# RX_V1.net
KiCad netlist of a schematic drawn in Altium Designer
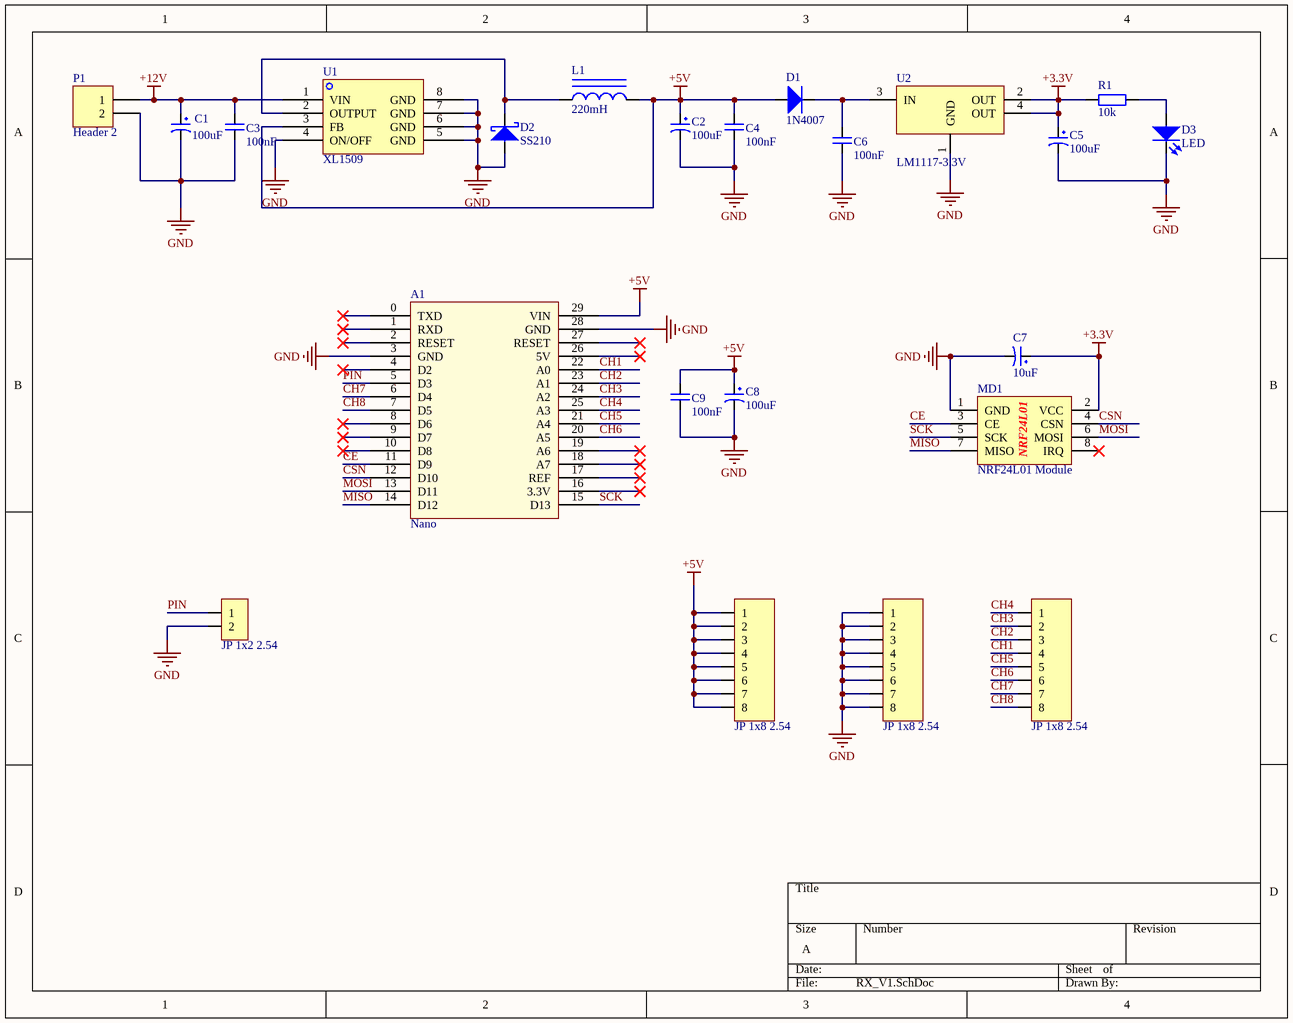
[diagram p0: RX_V1.SchDoc]

(export (version "E")
  (design (tool "Eeschema 10.0.6"))
  (components
    (comp (ref "A1")
      (value "Nano")
      (footprint "Arduino nano")
      (libsource (lib "Altium_Lib_by_KhueNguyenCreator") (part "Arduino Nano"))
    )
    (comp (ref "C1")
      (value "100uF")
      (footprint "tu hoa 5mm")
      (description "Cắm")
      (libsource (lib "Altium_Lib_by_KhueNguyenCreator") (part "Tu Hoa 100uF 25V 6x11"))
    )
    (comp (ref "C2")
      (value "100uF")
      (footprint "tu hoa 5mm")
      (description "Cắm")
      (libsource (lib "Altium_Lib_by_KhueNguyenCreator") (part "Tu Hoa 100uF 25V 6x11"))
    )
    (comp (ref "C3")
      (value "100nF")
      (footprint "CN1")
      (libsource (lib "Electronic4u") (part "Cap_Non-Polar"))
    )
    (comp (ref "C4")
      (value "100nF")
      (footprint "CN1")
      (libsource (lib "Electronic4u") (part "Cap_Non-Polar"))
    )
    (comp (ref "C5")
      (value "100uF")
      (footprint "tu hoa 5mm")
      (description "Cắm")
      (libsource (lib "Altium_Lib_by_KhueNguyenCreator") (part "Tu Hoa 100uF 25V 6x11"))
    )
    (comp (ref "C6")
      (value "100nF")
      (footprint "CN1")
      (libsource (lib "Electronic4u") (part "Cap_Non-Polar"))
    )
    (comp (ref "C7")
      (value "10uF")
      (footprint "tu hoa 5mm")
      (description "Cắm")
      (libsource (lib "") (part "Tu Hoa 100uF 25V 6x11_1"))
    )
    (comp (ref "C8")
      (value "100uF")
      (footprint "tu hoa 5mm")
      (description "Cắm")
      (libsource (lib "Altium_Lib_by_KhueNguyenCreator") (part "Tu Hoa 100uF 25V 6x11"))
    )
    (comp (ref "C9")
      (value "100nF")
      (footprint "CN1")
      (libsource (lib "Electronic4u") (part "Cap_Non-Polar"))
    )
    (comp (ref "D1")
      (value "1N4007")
      (footprint "DO-201AD-V")
      (description "Diode Standard")
      (fields (field (name "PART NUMBER") "LED 3 ly Single Colour"))
      (libsource (lib "Electronic4u") (part "Diode Standard"))
    )
    (comp (ref "D2")
      (value "SS210")
      (footprint "DO-214AC")
      (description "Diode Schottky")
      (fields (field (name "PART NUMBER") "LED 3 ly Single Colour"))
      (libsource (lib "Electronic4u") (part "Diode Schottky"))
    )
    (comp (ref "D3")
      (value "LED")
      (footprint "LED-3MM RED")
      (description "LED Single")
      (libsource (lib "Electronic4u") (part "LED"))
    )
    (comp (ref "JP1")
      (value "JP 1x2 2.54")
      (footprint "JP 1x2 DT")
      (description "Cắm")
      (libsource (lib "Altium_Lib_by_KhueNguyenCreator") (part "JP 1x2 2.54 Duc Thang"))
    )
    (comp (ref "JP2")
      (value "JP 1x8 2.54")
      (footprint "JP 1x8 DT")
      (description "Cắm")
      (libsource (lib "Altium_Lib_by_KhueNguyenCreator") (part "JP 1x8 2.54 Duc Thang"))
    )
    (comp (ref "JP3")
      (value "JP 1x8 2.54")
      (footprint "JP 1x8 DT")
      (description "Cắm")
      (libsource (lib "Altium_Lib_by_KhueNguyenCreator") (part "JP 1x8 2.54 Duc Thang"))
    )
    (comp (ref "JP4")
      (value "JP 1x8 2.54")
      (footprint "JP 1x8 DT")
      (description "Cắm")
      (libsource (lib "Altium_Lib_by_KhueNguyenCreator") (part "JP 1x8 2.54 Duc Thang"))
    )
    (comp (ref "L1")
      (value "220mH")
      (footprint "INDUCTOR SMD 7342 7.3X7.3X4.2mm")
      (description "Magnetic-Core Inductor")
      (libsource (lib "Electronic4u") (part "Inductor Iron"))
    )
    (comp (ref "MD1")
      (value "NRF24L01 Module")
      (footprint "NRF24L01")
      (libsource (lib "Altium_Lib_by_KhueNguyenCreator") (part "NRF24L01 Module"))
    )
    (comp (ref "P1")
      (value "Header 2")
      (footprint "HED2T")
      (description "Header, 2-Pin")
      (fields (field (name "PUBLISHER") "Altium Limited"))
      (libsource (lib "Electronic4u") (part "Header 2"))
    )
    (comp (ref "R1")
      (value "10k")
      (footprint "RESISTOR 1/4W")
      (libsource (lib "Electronic4u") (part "Resistor"))
    )
    (comp (ref "U1")
      (value "XL1509")
      (footprint "SOP8")
      (description "IC power sop8")
      (libsource (lib "FMS_PcbLib1") (part "XL1509"))
    )
    (comp (ref "U2")
      (value "LM1117-3.3V")
      (footprint "SOT223-4N")
      (description "800mA Low-Dropout Linear Regulator")
      (fields (field (name "CREATOR") "Nguyen Ba Bien"))
      (libsource (lib "Electronic4u") (part "LM1117"))
    )
  )
  (nets
    (net (code "1") (name "+3.3V") (class "Default")
      (node (ref "C5") (pin "1") (pinfunction "1_1") (pintype "passive"))
      (node (ref "C7") (pin "1") (pinfunction "1_1") (pintype "passive"))
      (node (ref "MD1") (pin "2") (pinfunction "VCC_2") (pintype "passive"))
      (node (ref "R1") (pin "1") (pinfunction "1_1") (pintype "passive"))
      (node (ref "U2") (pin "2") (pinfunction "OUT_2") (pintype "passive"))
      (node (ref "U2") (pin "4") (pinfunction "OUT_4") (pintype "passive"))
    )
    (net (code "2") (name "+5V") (class "Default")
      (node (ref "A1") (pin "29") (pinfunction "VIN_29") (pintype "passive"))
      (node (ref "C2") (pin "1") (pinfunction "1_1") (pintype "passive"))
      (node (ref "C4") (pin "2") (pinfunction "2_2") (pintype "passive"))
      (node (ref "C8") (pin "1") (pinfunction "1_1") (pintype "passive"))
      (node (ref "C9") (pin "2") (pinfunction "2_2") (pintype "passive"))
      (node (ref "D1") (pin "1") (pinfunction "1_1") (pintype "passive"))
      (node (ref "JP2") (pin "1") (pinfunction "1_1") (pintype "passive"))
      (node (ref "JP2") (pin "2") (pinfunction "2_2") (pintype "passive"))
      (node (ref "JP2") (pin "3") (pinfunction "3_3") (pintype "passive"))
      (node (ref "JP2") (pin "4") (pinfunction "4_4") (pintype "passive"))
      (node (ref "JP2") (pin "5") (pinfunction "5_5") (pintype "passive"))
      (node (ref "JP2") (pin "6") (pinfunction "6_6") (pintype "passive"))
      (node (ref "JP2") (pin "7") (pinfunction "7_7") (pintype "passive"))
      (node (ref "JP2") (pin "8") (pinfunction "8_8") (pintype "passive"))
      (node (ref "L1") (pin "2") (pinfunction "2_2") (pintype "passive"))
      (node (ref "U1") (pin "3") (pinfunction "FB_3") (pintype "passive"))
    )
    (net (code "3") (name "+12V") (class "Default")
      (node (ref "C1") (pin "1") (pinfunction "1_1") (pintype "passive"))
      (node (ref "C3") (pin "2") (pinfunction "2_2") (pintype "passive"))
      (node (ref "P1") (pin "1") (pinfunction "1_1") (pintype "passive"))
      (node (ref "U1") (pin "1") (pinfunction "VIN_1") (pintype "passive"))
    )
    (net (code "4") (name "/CE") (class "Default")
      (node (ref "A1") (pin "11") (pinfunction "D9_11") (pintype "passive"))
      (node (ref "MD1") (pin "3") (pinfunction "CE_3") (pintype "passive"))
    )
    (net (code "5") (name "/CH1") (class "Default")
      (node (ref "A1") (pin "22") (pinfunction "A0_22") (pintype "passive"))
      (node (ref "JP4") (pin "4") (pinfunction "4_4") (pintype "passive"))
    )
    (net (code "6") (name "/CH2") (class "Default")
      (node (ref "A1") (pin "23") (pinfunction "A1_23") (pintype "passive"))
      (node (ref "JP4") (pin "3") (pinfunction "3_3") (pintype "passive"))
    )
    (net (code "7") (name "/CH3") (class "Default")
      (node (ref "A1") (pin "24") (pinfunction "A2_24") (pintype "passive"))
      (node (ref "JP4") (pin "2") (pinfunction "2_2") (pintype "passive"))
    )
    (net (code "8") (name "/CH4") (class "Default")
      (node (ref "A1") (pin "25") (pinfunction "A3_25") (pintype "passive"))
      (node (ref "JP4") (pin "1") (pinfunction "1_1") (pintype "passive"))
    )
    (net (code "9") (name "/CH5") (class "Default")
      (node (ref "A1") (pin "21") (pinfunction "A4_21") (pintype "passive"))
      (node (ref "JP4") (pin "5") (pinfunction "5_5") (pintype "passive"))
    )
    (net (code "10") (name "/CH6") (class "Default")
      (node (ref "A1") (pin "20") (pinfunction "A5_20") (pintype "passive"))
      (node (ref "JP4") (pin "6") (pinfunction "6_6") (pintype "passive"))
    )
    (net (code "11") (name "/CH7") (class "Default")
      (node (ref "A1") (pin "6") (pinfunction "D4_6") (pintype "passive"))
      (node (ref "JP4") (pin "7") (pinfunction "7_7") (pintype "passive"))
    )
    (net (code "12") (name "/CH8") (class "Default")
      (node (ref "A1") (pin "7") (pinfunction "D5_7") (pintype "passive"))
      (node (ref "JP4") (pin "8") (pinfunction "8_8") (pintype "passive"))
    )
    (net (code "13") (name "/CSN") (class "Default")
      (node (ref "A1") (pin "12") (pinfunction "D10_12") (pintype "passive"))
      (node (ref "MD1") (pin "4") (pinfunction "CSN_4") (pintype "passive"))
    )
    (net (code "14") (name "/MISO") (class "Default")
      (node (ref "A1") (pin "14") (pinfunction "D12_14") (pintype "passive"))
      (node (ref "MD1") (pin "7") (pinfunction "MISO_7") (pintype "passive"))
    )
    (net (code "15") (name "/MOSI") (class "Default")
      (node (ref "A1") (pin "13") (pinfunction "D11_13") (pintype "passive"))
      (node (ref "MD1") (pin "6") (pinfunction "MOSI_6") (pintype "passive"))
    )
    (net (code "16") (name "/PIN") (class "Default")
      (node (ref "A1") (pin "5") (pinfunction "D3_5") (pintype "passive"))
      (node (ref "JP1") (pin "1") (pinfunction "1_1") (pintype "passive"))
    )
    (net (code "17") (name "/SCK") (class "Default")
      (node (ref "A1") (pin "15") (pinfunction "D13_15") (pintype "passive"))
      (node (ref "MD1") (pin "5") (pinfunction "SCK_5") (pintype "passive"))
    )
    (net (code "18") (name "GND") (class "Default")
      (node (ref "A1") (pin "28") (pinfunction "GND_28") (pintype "passive"))
      (node (ref "A1") (pin "3") (pinfunction "GND_3") (pintype "passive"))
      (node (ref "C1") (pin "2") (pinfunction "2_2") (pintype "passive"))
      (node (ref "C2") (pin "2") (pinfunction "2_2") (pintype "passive"))
      (node (ref "C3") (pin "1") (pinfunction "1_1") (pintype "passive"))
      (node (ref "C4") (pin "1") (pinfunction "1_1") (pintype "passive"))
      (node (ref "C5") (pin "2") (pinfunction "2_2") (pintype "passive"))
      (node (ref "C6") (pin "1") (pinfunction "1_1") (pintype "passive"))
      (node (ref "C7") (pin "2") (pinfunction "2_2") (pintype "passive"))
      (node (ref "C8") (pin "2") (pinfunction "2_2") (pintype "passive"))
      (node (ref "C9") (pin "1") (pinfunction "1_1") (pintype "passive"))
      (node (ref "D2") (pin "1") (pinfunction "1_1") (pintype "passive"))
      (node (ref "D3") (pin "2") (pinfunction "2_2") (pintype "passive"))
      (node (ref "JP1") (pin "2") (pinfunction "2_2") (pintype "passive"))
      (node (ref "JP3") (pin "1") (pinfunction "1_1") (pintype "passive"))
      (node (ref "JP3") (pin "2") (pinfunction "2_2") (pintype "passive"))
      (node (ref "JP3") (pin "3") (pinfunction "3_3") (pintype "passive"))
      (node (ref "JP3") (pin "4") (pinfunction "4_4") (pintype "passive"))
      (node (ref "JP3") (pin "5") (pinfunction "5_5") (pintype "passive"))
      (node (ref "JP3") (pin "6") (pinfunction "6_6") (pintype "passive"))
      (node (ref "JP3") (pin "7") (pinfunction "7_7") (pintype "passive"))
      (node (ref "JP3") (pin "8") (pinfunction "8_8") (pintype "passive"))
      (node (ref "MD1") (pin "1") (pinfunction "GND_1") (pintype "passive"))
      (node (ref "P1") (pin "2") (pinfunction "2_2") (pintype "passive"))
      (node (ref "U1") (pin "4") (pinfunction "ON/OFF_4") (pintype "passive"))
      (node (ref "U1") (pin "5") (pinfunction "GND_5") (pintype "passive"))
      (node (ref "U1") (pin "6") (pinfunction "GND_6") (pintype "passive"))
      (node (ref "U1") (pin "7") (pinfunction "GND_7") (pintype "passive"))
      (node (ref "U1") (pin "8") (pinfunction "GND_8") (pintype "passive"))
      (node (ref "U2") (pin "1") (pinfunction "GND_1") (pintype "passive"))
    )
    (net (code "19") (name "Net-(D3-Pad1)") (class "Default")
      (node (ref "D3") (pin "1") (pinfunction "1_1") (pintype "passive"))
      (node (ref "R1") (pin "2") (pinfunction "2_2") (pintype "passive"))
    )
    (net (code "20") (name "Net-(U1-OUTPUT)") (class "Default")
      (node (ref "D2") (pin "2") (pinfunction "2_2") (pintype "passive"))
      (node (ref "L1") (pin "1") (pinfunction "1_1") (pintype "passive"))
      (node (ref "U1") (pin "2") (pinfunction "OUTPUT_2") (pintype "passive"))
    )
    (net (code "21") (name "Net-(U2-IN)") (class "Default")
      (node (ref "C6") (pin "2") (pinfunction "2_2") (pintype "passive"))
      (node (ref "D1") (pin "2") (pinfunction "2_2") (pintype "passive"))
      (node (ref "U2") (pin "3") (pinfunction "IN_3") (pintype "passive"))
    )
    (net (code "22") (name "unconnected-(A1-3.3V-Pad16)") (class "Default")
      (node (ref "A1") (pin "16") (pinfunction "3.3V_16") (pintype "passive+no_connect"))
    )
    (net (code "23") (name "unconnected-(A1-5V-Pad26)") (class "Default")
      (node (ref "A1") (pin "26") (pinfunction "5V_26") (pintype "passive+no_connect"))
    )
    (net (code "24") (name "unconnected-(A1-A6-Pad19)") (class "Default")
      (node (ref "A1") (pin "19") (pinfunction "A6_19") (pintype "passive+no_connect"))
    )
    (net (code "25") (name "unconnected-(A1-A7-Pad18)") (class "Default")
      (node (ref "A1") (pin "18") (pinfunction "A7_18") (pintype "passive+no_connect"))
    )
    (net (code "26") (name "unconnected-(A1-D2-Pad4)") (class "Default")
      (node (ref "A1") (pin "4") (pinfunction "D2_4") (pintype "passive+no_connect"))
    )
    (net (code "27") (name "unconnected-(A1-D6-Pad8)") (class "Default")
      (node (ref "A1") (pin "8") (pinfunction "D6_8") (pintype "passive+no_connect"))
    )
    (net (code "28") (name "unconnected-(A1-D7-Pad9)") (class "Default")
      (node (ref "A1") (pin "9") (pinfunction "D7_9") (pintype "passive+no_connect"))
    )
    (net (code "29") (name "unconnected-(A1-D8-Pad10)") (class "Default")
      (node (ref "A1") (pin "10") (pinfunction "D8_10") (pintype "passive+no_connect"))
    )
    (net (code "30") (name "unconnected-(A1-REF-Pad17)") (class "Default")
      (node (ref "A1") (pin "17") (pinfunction "REF_17") (pintype "passive+no_connect"))
    )
    (net (code "31") (name "unconnected-(A1-RESET-Pad2)") (class "Default")
      (node (ref "A1") (pin "2") (pinfunction "RESET_2") (pintype "passive+no_connect"))
    )
    (net (code "32") (name "unconnected-(A1-RESET-Pad27)") (class "Default")
      (node (ref "A1") (pin "27") (pinfunction "RESET_27") (pintype "passive+no_connect"))
    )
    (net (code "33") (name "unconnected-(A1-RXD-Pad1)") (class "Default")
      (node (ref "A1") (pin "1") (pinfunction "RXD_1") (pintype "passive+no_connect"))
    )
    (net (code "34") (name "unconnected-(A1-TXD-Pad0)") (class "Default")
      (node (ref "A1") (pin "0") (pinfunction "TXD_0") (pintype "passive+no_connect"))
    )
    (net (code "35") (name "unconnected-(MD1-IRQ-Pad8)") (class "Default")
      (node (ref "MD1") (pin "8") (pinfunction "IRQ_8") (pintype "passive+no_connect"))
    )
  )
)
